# master_node_1284p.net
KiCad netlist of a schematic drawn in EAGLE
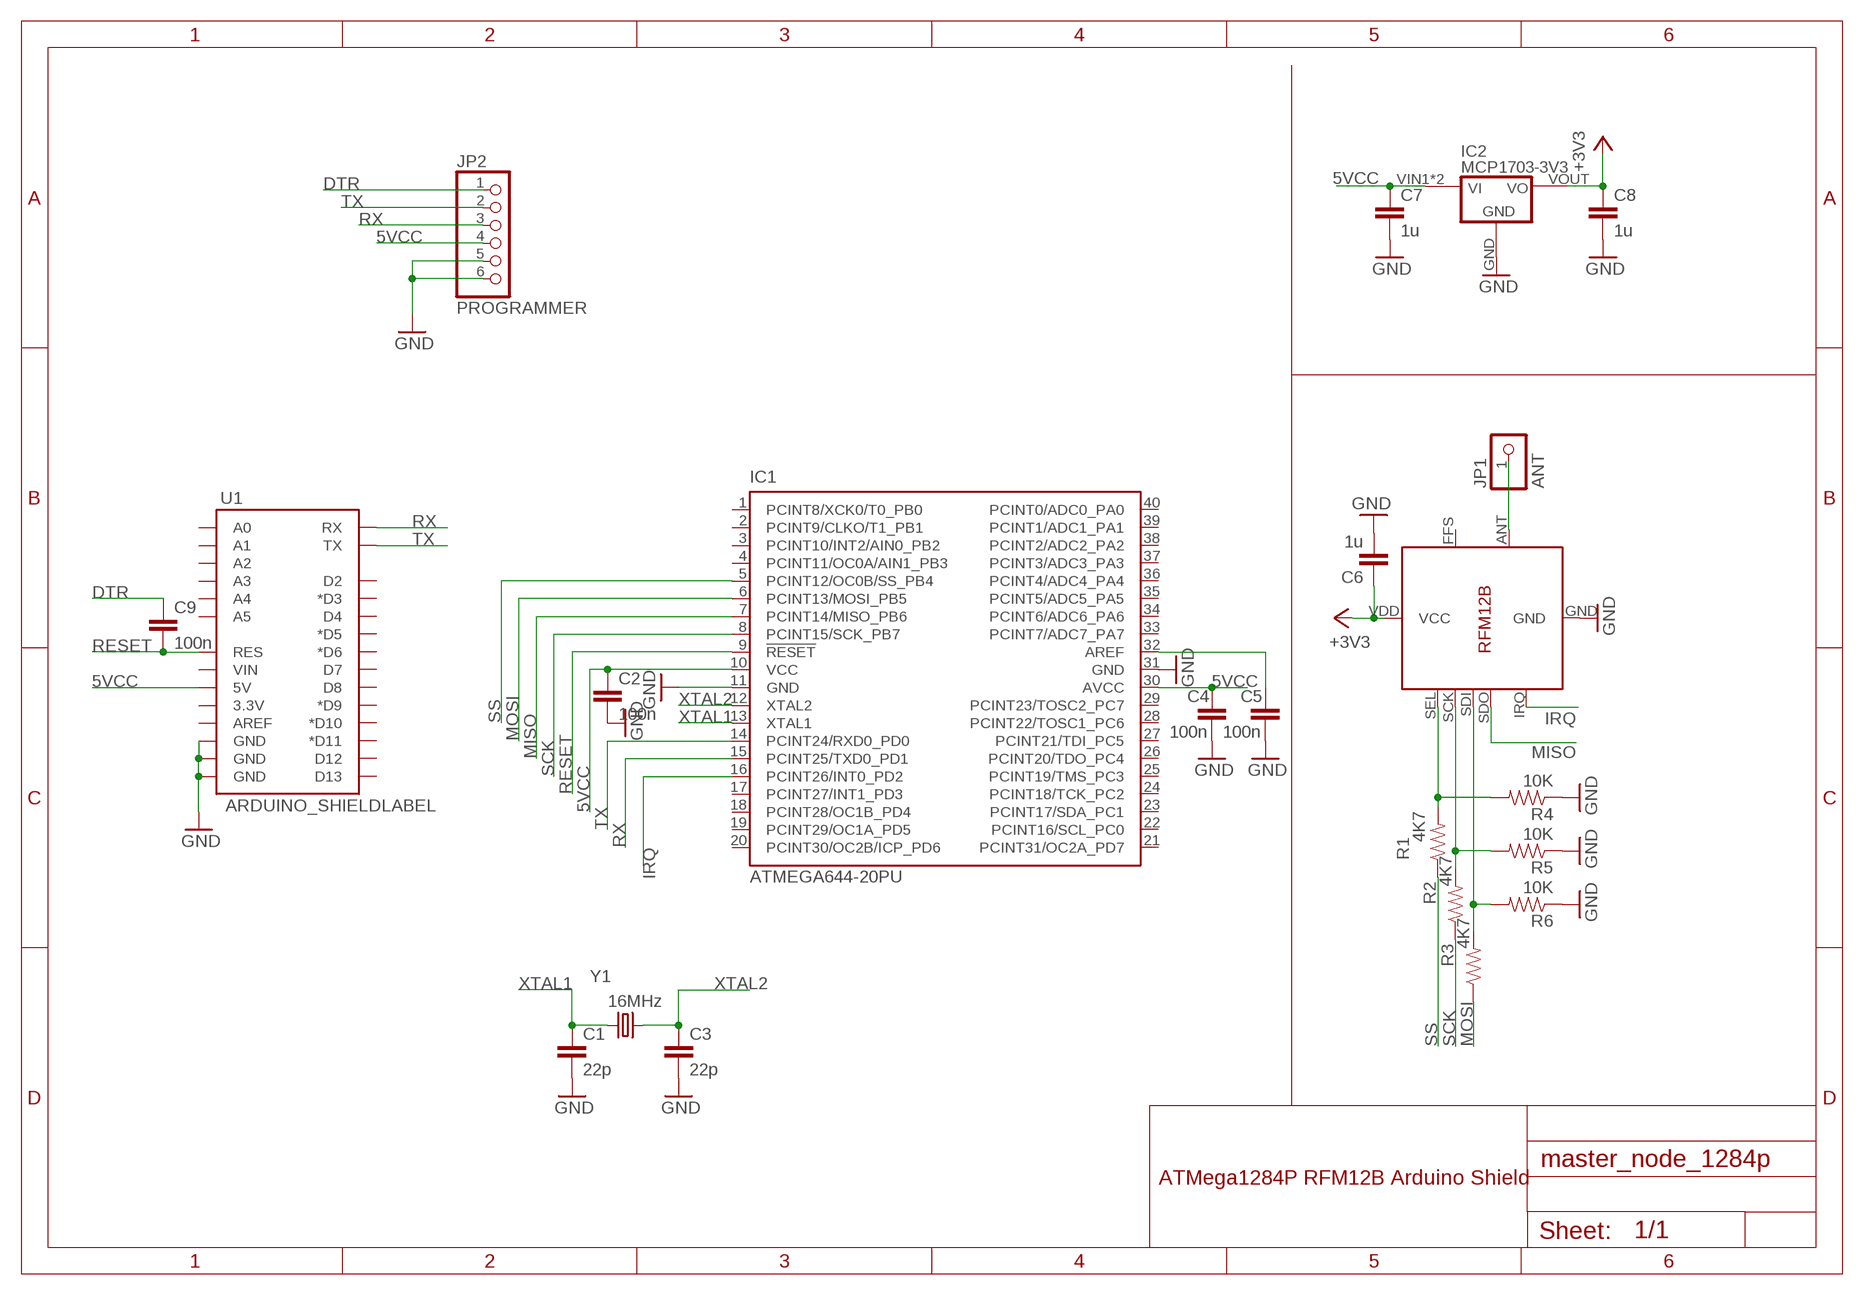
[diagram p0: schematic, sheet 1]

(export (version "E")
  (design (tool "Eeschema 10.0.6"))
  (components
    (comp (ref "C1")
      (value "22p")
      (footprint "eagle-import:C0805K")
      (libsource (lib "eagle-import") (part "C-EUC0805K"))
    )
    (comp (ref "C2")
      (value "100n")
      (footprint "eagle-import:C0805K")
      (libsource (lib "eagle-import") (part "C-EUC0805K"))
    )
    (comp (ref "C3")
      (value "22p")
      (footprint "eagle-import:C0805K")
      (libsource (lib "eagle-import") (part "C-EUC0805K"))
    )
    (comp (ref "C4")
      (value "100n")
      (footprint "eagle-import:C0805K")
      (libsource (lib "eagle-import") (part "C-EUC0805K"))
    )
    (comp (ref "C5")
      (value "100n")
      (footprint "eagle-import:C0805K")
      (libsource (lib "eagle-import") (part "C-EUC0805K"))
    )
    (comp (ref "C6")
      (value "1u")
      (footprint "eagle-import:0805")
      (libsource (lib "eagle-import") (part "CAP0805"))
    )
    (comp (ref "C7")
      (value "1u")
      (footprint "eagle-import:0805")
      (libsource (lib "eagle-import") (part "CAP0805"))
    )
    (comp (ref "C8")
      (value "1u")
      (footprint "eagle-import:0805")
      (libsource (lib "eagle-import") (part "CAP0805"))
    )
    (comp (ref "C9")
      (value "100n")
      (footprint "eagle-import:C0805K")
      (libsource (lib "eagle-import") (part "C-EUC0805K"))
    )
    (comp (ref "IC1")
      (value "ATMEGA644-20PU")
      (footprint "eagle-import:DIL40")
      (libsource (lib "eagle-import") (part "ATMEGA644-PU20"))
    )
    (comp (ref "IC2")
      (value "MCP1703-3V3")
      (footprint "eagle-import:MCP1703-SOT89")
      (libsource (lib "eagle-import") (part "MCP1703-SOT89"))
    )
    (comp (ref "JP1")
      (value "ANT")
      (footprint "eagle-import:1X01")
      (libsource (lib "eagle-import") (part "PINHD-1X1"))
    )
    (comp (ref "JP2")
      (value "PROGRAMMER")
      (footprint "eagle-import:1X06_90")
      (libsource (lib "eagle-import") (part "PINHD-1X6/90"))
    )
    (comp (ref "R1")
      (value "4K7")
      (footprint "eagle-import:0805")
      (libsource (lib "eagle-import") (part "RESISTOR0805-RES"))
    )
    (comp (ref "R2")
      (value "4K7")
      (footprint "eagle-import:0805")
      (libsource (lib "eagle-import") (part "RESISTOR0805-RES"))
    )
    (comp (ref "R3")
      (value "4K7")
      (footprint "eagle-import:0805")
      (libsource (lib "eagle-import") (part "RESISTOR0805-RES"))
    )
    (comp (ref "R4")
      (value "10K")
      (footprint "eagle-import:0805")
      (libsource (lib "eagle-import") (part "RESISTOR0805-RES"))
    )
    (comp (ref "R5")
      (value "10K")
      (footprint "eagle-import:0805")
      (libsource (lib "eagle-import") (part "RESISTOR0805-RES"))
    )
    (comp (ref "R6")
      (value "10K")
      (footprint "eagle-import:0805")
      (libsource (lib "eagle-import") (part "RESISTOR0805-RES"))
    )
    (comp (ref "U$1")
      (value "RFM12B")
      (footprint "eagle-import:RFM12B")
      (libsource (lib "eagle-import") (part "RFM12B"))
    )
    (comp (ref "U1")
      (value "ARDUINO_SHIELDLABEL")
      (footprint "eagle-import:DUEMILANOVE_SHIELD")
      (libsource (lib "eagle-import") (part "ARDUINO_SHIELDLABEL"))
    )
    (comp (ref "Y1")
      (value "16MHz")
      (footprint "eagle-import:HC49US")
      (libsource (lib "eagle-import") (part "CRYSTALHC49US"))
    )
  )
  (nets
    (net (code "1") (name "+3V3") (class "Default")
      (node (ref "C6") (pin "1") (pinfunction "1_1") (pintype "passive"))
      (node (ref "C8") (pin "1") (pinfunction "1_1") (pintype "passive"))
      (node (ref "IC2") (pin "VOUT") (pinfunction "VO_VOUT") (pintype "passive"))
      (node (ref "U$1") (pin "VDD") (pinfunction "VCC_VDD") (pintype "power_in"))
    )
    (net (code "2") (name "/5VCC") (class "Default")
      (node (ref "C2") (pin "1") (pinfunction "1_1") (pintype "passive"))
      (node (ref "C4") (pin "1") (pinfunction "1_1") (pintype "passive"))
      (node (ref "C7") (pin "1") (pinfunction "1_1") (pintype "passive"))
      (node (ref "IC1") (pin "10") (pinfunction "VCC_10") (pintype "power_in"))
      (node (ref "IC1") (pin "30") (pinfunction "AVCC_30") (pintype "power_in"))
      (node (ref "IC2") (pin "VIN1") (pinfunction "VI_VIN1") (pintype "power_in"))
      (node (ref "IC2") (pin "VIN2") (pinfunction "VI_VIN2") (pintype "power_in"))
      (node (ref "JP2") (pin "4") (pinfunction "4_4") (pintype "passive"))
      (node (ref "U1") (pin "5V") (pinfunction "5V_5V") (pintype "bidirectional"))
    )
    (net (code "3") (name "/DTR") (class "Default")
      (node (ref "C9") (pin "1") (pinfunction "1_1") (pintype "passive"))
      (node (ref "JP2") (pin "1") (pinfunction "1_1") (pintype "passive"))
    )
    (net (code "4") (name "/IRQ") (class "Default")
      (node (ref "IC1") (pin "16") (pinfunction "PCINT26/INT0_PD2_16") (pintype "bidirectional"))
      (node (ref "U$1") (pin "IRQ") (pinfunction "IRQ_IRQ") (pintype "open_collector"))
    )
    (net (code "5") (name "/MISO") (class "Default")
      (node (ref "IC1") (pin "7") (pinfunction "PCINT14/MISO_PB6_7") (pintype "bidirectional"))
      (node (ref "U$1") (pin "SDO") (pinfunction "SDO_SDO") (pintype "output"))
    )
    (net (code "6") (name "/MOSI") (class "Default")
      (node (ref "IC1") (pin "6") (pinfunction "PCINT13/MOSI_PB5_6") (pintype "bidirectional"))
      (node (ref "R3") (pin "1") (pinfunction "1_1") (pintype "passive"))
    )
    (net (code "7") (name "/RESET") (class "Default")
      (node (ref "C9") (pin "2") (pinfunction "2_2") (pintype "passive"))
      (node (ref "IC1") (pin "9") (pinfunction "~{RESET}_9") (pintype "input"))
      (node (ref "U1") (pin "RES") (pinfunction "RES_RES") (pintype "bidirectional"))
    )
    (net (code "8") (name "/RX") (class "Default")
      (node (ref "IC1") (pin "15") (pinfunction "PCINT25/TXD0_PD1_15") (pintype "bidirectional"))
      (node (ref "JP2") (pin "3") (pinfunction "3_3") (pintype "passive"))
      (node (ref "U1") (pin "RX") (pinfunction "RX_RX") (pintype "bidirectional"))
    )
    (net (code "9") (name "/SCK") (class "Default")
      (node (ref "IC1") (pin "8") (pinfunction "PCINT15/SCK_PB7_8") (pintype "bidirectional"))
      (node (ref "R2") (pin "1") (pinfunction "1_1") (pintype "passive"))
    )
    (net (code "10") (name "/SS") (class "Default")
      (node (ref "IC1") (pin "5") (pinfunction "PCINT12/OC0B/SS_PB4_5") (pintype "bidirectional"))
      (node (ref "R1") (pin "1") (pinfunction "1_1") (pintype "passive"))
    )
    (net (code "11") (name "/TX") (class "Default")
      (node (ref "IC1") (pin "14") (pinfunction "PCINT24/RXD0_PD0_14") (pintype "bidirectional"))
      (node (ref "JP2") (pin "2") (pinfunction "2_2") (pintype "passive"))
      (node (ref "U1") (pin "TX") (pinfunction "TX_TX") (pintype "bidirectional"))
    )
    (net (code "12") (name "/XTAL1") (class "Default")
      (node (ref "C1") (pin "1") (pinfunction "1_1") (pintype "passive"))
      (node (ref "IC1") (pin "13") (pinfunction "XTAL1_13") (pintype "input"))
      (node (ref "Y1") (pin "1") (pinfunction "1_1") (pintype "passive"))
    )
    (net (code "13") (name "/XTAL2") (class "Default")
      (node (ref "C3") (pin "1") (pinfunction "1_1") (pintype "passive"))
      (node (ref "IC1") (pin "12") (pinfunction "XTAL2_12") (pintype "output"))
      (node (ref "Y1") (pin "2") (pinfunction "2_2") (pintype "passive"))
    )
    (net (code "14") (name "GND") (class "Default")
      (node (ref "C1") (pin "2") (pinfunction "2_2") (pintype "passive"))
      (node (ref "C2") (pin "2") (pinfunction "2_2") (pintype "passive"))
      (node (ref "C3") (pin "2") (pinfunction "2_2") (pintype "passive"))
      (node (ref "C4") (pin "2") (pinfunction "2_2") (pintype "passive"))
      (node (ref "C5") (pin "2") (pinfunction "2_2") (pintype "passive"))
      (node (ref "C6") (pin "2") (pinfunction "2_2") (pintype "passive"))
      (node (ref "C7") (pin "2") (pinfunction "2_2") (pintype "passive"))
      (node (ref "C8") (pin "2") (pinfunction "2_2") (pintype "passive"))
      (node (ref "IC1") (pin "11") (pinfunction "GND_11") (pintype "power_in"))
      (node (ref "IC1") (pin "31") (pinfunction "GND_31") (pintype "power_in"))
      (node (ref "IC2") (pin "GND") (pinfunction "GND_GND") (pintype "power_in"))
      (node (ref "JP2") (pin "5") (pinfunction "5_5") (pintype "passive"))
      (node (ref "JP2") (pin "6") (pinfunction "6_6") (pintype "passive"))
      (node (ref "R4") (pin "1") (pinfunction "1_1") (pintype "passive"))
      (node (ref "R5") (pin "1") (pinfunction "1_1") (pintype "passive"))
      (node (ref "R6") (pin "1") (pinfunction "1_1") (pintype "passive"))
      (node (ref "U$1") (pin "GND") (pinfunction "GND_GND") (pintype "power_in"))
      (node (ref "U1") (pin "GND@0") (pinfunction "GND_GND@0") (pintype "bidirectional"))
      (node (ref "U1") (pin "GND@1") (pinfunction "GND_GND@1") (pintype "bidirectional"))
      (node (ref "U1") (pin "GND@2") (pinfunction "GND_GND@2") (pintype "bidirectional"))
    )
    (net (code "15") (name "Net-(IC1-AREF)") (class "Default")
      (node (ref "C5") (pin "1") (pinfunction "1_1") (pintype "passive"))
      (node (ref "IC1") (pin "32") (pinfunction "AREF_32") (pintype "passive"))
    )
    (net (code "16") (name "Net-(JP1-Pad1)") (class "Default")
      (node (ref "JP1") (pin "1") (pinfunction "1_1") (pintype "passive"))
      (node (ref "U$1") (pin "ANT") (pinfunction "ANT_ANT") (pintype "passive"))
    )
    (net (code "17") (name "Net-(R1-Pad2)") (class "Default")
      (node (ref "R1") (pin "2") (pinfunction "2_2") (pintype "passive"))
      (node (ref "R4") (pin "2") (pinfunction "2_2") (pintype "passive"))
      (node (ref "U$1") (pin "SEL") (pinfunction "SEL_SEL") (pintype "input"))
    )
    (net (code "18") (name "Net-(R2-Pad2)") (class "Default")
      (node (ref "R2") (pin "2") (pinfunction "2_2") (pintype "passive"))
      (node (ref "R5") (pin "2") (pinfunction "2_2") (pintype "passive"))
      (node (ref "U$1") (pin "SCK") (pinfunction "SCK_SCK") (pintype "input"))
    )
    (net (code "19") (name "Net-(R3-Pad2)") (class "Default")
      (node (ref "R3") (pin "2") (pinfunction "2_2") (pintype "passive"))
      (node (ref "R6") (pin "2") (pinfunction "2_2") (pintype "passive"))
      (node (ref "U$1") (pin "SDI") (pinfunction "SDI_SDI") (pintype "input"))
    )
    (net (code "20") (name "unconnected-(IC1-PCINT0{slash}ADC0_PA0-Pad40)") (class "Default")
      (node (ref "IC1") (pin "40") (pinfunction "PCINT0/ADC0_PA0_40") (pintype "bidirectional"))
    )
    (net (code "21") (name "unconnected-(IC1-PCINT1{slash}ADC1_PA1-Pad39)") (class "Default")
      (node (ref "IC1") (pin "39") (pinfunction "PCINT1/ADC1_PA1_39") (pintype "bidirectional"))
    )
    (net (code "22") (name "unconnected-(IC1-PCINT2{slash}ADC2_PA2-Pad38)") (class "Default")
      (node (ref "IC1") (pin "38") (pinfunction "PCINT2/ADC2_PA2_38") (pintype "bidirectional"))
    )
    (net (code "23") (name "unconnected-(IC1-PCINT3{slash}ADC3_PA3-Pad37)") (class "Default")
      (node (ref "IC1") (pin "37") (pinfunction "PCINT3/ADC3_PA3_37") (pintype "bidirectional"))
    )
    (net (code "24") (name "unconnected-(IC1-PCINT4{slash}ADC4_PA4-Pad36)") (class "Default")
      (node (ref "IC1") (pin "36") (pinfunction "PCINT4/ADC4_PA4_36") (pintype "bidirectional"))
    )
    (net (code "25") (name "unconnected-(IC1-PCINT5{slash}ADC5_PA5-Pad35)") (class "Default")
      (node (ref "IC1") (pin "35") (pinfunction "PCINT5/ADC5_PA5_35") (pintype "bidirectional"))
    )
    (net (code "26") (name "unconnected-(IC1-PCINT6{slash}ADC6_PA6-Pad34)") (class "Default")
      (node (ref "IC1") (pin "34") (pinfunction "PCINT6/ADC6_PA6_34") (pintype "bidirectional"))
    )
    (net (code "27") (name "unconnected-(IC1-PCINT7{slash}ADC7_PA7-Pad33)") (class "Default")
      (node (ref "IC1") (pin "33") (pinfunction "PCINT7/ADC7_PA7_33") (pintype "bidirectional"))
    )
    (net (code "28") (name "unconnected-(IC1-PCINT8{slash}XCK0{slash}T0_PB0-Pad1)") (class "Default")
      (node (ref "IC1") (pin "1") (pinfunction "PCINT8/XCK0/T0_PB0_1") (pintype "bidirectional"))
    )
    (net (code "29") (name "unconnected-(IC1-PCINT9{slash}CLKO{slash}T1_PB1-Pad2)") (class "Default")
      (node (ref "IC1") (pin "2") (pinfunction "PCINT9/CLKO/T1_PB1_2") (pintype "bidirectional"))
    )
    (net (code "30") (name "unconnected-(IC1-PCINT10{slash}INT2{slash}AIN0_PB2-Pad3)") (class "Default")
      (node (ref "IC1") (pin "3") (pinfunction "PCINT10/INT2/AIN0_PB2_3") (pintype "bidirectional"))
    )
    (net (code "31") (name "unconnected-(IC1-PCINT11{slash}OC0A{slash}AIN1_PB3-Pad4)") (class "Default")
      (node (ref "IC1") (pin "4") (pinfunction "PCINT11/OC0A/AIN1_PB3_4") (pintype "bidirectional"))
    )
    (net (code "32") (name "unconnected-(IC1-PCINT16{slash}SCL_PC0-Pad22)") (class "Default")
      (node (ref "IC1") (pin "22") (pinfunction "PCINT16/SCL_PC0_22") (pintype "bidirectional"))
    )
    (net (code "33") (name "unconnected-(IC1-PCINT17{slash}SDA_PC1-Pad23)") (class "Default")
      (node (ref "IC1") (pin "23") (pinfunction "PCINT17/SDA_PC1_23") (pintype "bidirectional"))
    )
    (net (code "34") (name "unconnected-(IC1-PCINT18{slash}TCK_PC2-Pad24)") (class "Default")
      (node (ref "IC1") (pin "24") (pinfunction "PCINT18/TCK_PC2_24") (pintype "bidirectional"))
    )
    (net (code "35") (name "unconnected-(IC1-PCINT19{slash}TMS_PC3-Pad25)") (class "Default")
      (node (ref "IC1") (pin "25") (pinfunction "PCINT19/TMS_PC3_25") (pintype "bidirectional"))
    )
    (net (code "36") (name "unconnected-(IC1-PCINT20{slash}TDO_PC4-Pad26)") (class "Default")
      (node (ref "IC1") (pin "26") (pinfunction "PCINT20/TDO_PC4_26") (pintype "bidirectional"))
    )
    (net (code "37") (name "unconnected-(IC1-PCINT21{slash}TDI_PC5-Pad27)") (class "Default")
      (node (ref "IC1") (pin "27") (pinfunction "PCINT21/TDI_PC5_27") (pintype "bidirectional"))
    )
    (net (code "38") (name "unconnected-(IC1-PCINT22{slash}TOSC1_PC6-Pad28)") (class "Default")
      (node (ref "IC1") (pin "28") (pinfunction "PCINT22/TOSC1_PC6_28") (pintype "bidirectional"))
    )
    (net (code "39") (name "unconnected-(IC1-PCINT23{slash}TOSC2_PC7-Pad29)") (class "Default")
      (node (ref "IC1") (pin "29") (pinfunction "PCINT23/TOSC2_PC7_29") (pintype "bidirectional"))
    )
    (net (code "40") (name "unconnected-(IC1-PCINT27{slash}INT1_PD3-Pad17)") (class "Default")
      (node (ref "IC1") (pin "17") (pinfunction "PCINT27/INT1_PD3_17") (pintype "bidirectional"))
    )
    (net (code "41") (name "unconnected-(IC1-PCINT28{slash}OC1B_PD4-Pad18)") (class "Default")
      (node (ref "IC1") (pin "18") (pinfunction "PCINT28/OC1B_PD4_18") (pintype "bidirectional"))
    )
    (net (code "42") (name "unconnected-(IC1-PCINT29{slash}OC1A_PD5-Pad19)") (class "Default")
      (node (ref "IC1") (pin "19") (pinfunction "PCINT29/OC1A_PD5_19") (pintype "bidirectional"))
    )
    (net (code "43") (name "unconnected-(IC1-PCINT30{slash}OC2B{slash}ICP_PD6-Pad20)") (class "Default")
      (node (ref "IC1") (pin "20") (pinfunction "PCINT30/OC2B/ICP_PD6_20") (pintype "bidirectional"))
    )
    (net (code "44") (name "unconnected-(IC1-PCINT31{slash}OC2A_PD7-Pad21)") (class "Default")
      (node (ref "IC1") (pin "21") (pinfunction "PCINT31/OC2A_PD7_21") (pintype "bidirectional"))
    )
    (net (code "45") (name "unconnected-(U$1-PadFFS)") (class "Default")
      (node (ref "U$1") (pin "FFS") (pinfunction "FFS_FFS") (pintype "bidirectional"))
    )
    (net (code "46") (name "unconnected-(U1-*D3-PadD3)") (class "Default")
      (node (ref "U1") (pin "D3") (pinfunction "*D3_D3") (pintype "bidirectional"))
    )
    (net (code "47") (name "unconnected-(U1-*D5-PadD5)") (class "Default")
      (node (ref "U1") (pin "D5") (pinfunction "*D5_D5") (pintype "bidirectional"))
    )
    (net (code "48") (name "unconnected-(U1-*D6-PadD6)") (class "Default")
      (node (ref "U1") (pin "D6") (pinfunction "*D6_D6") (pintype "bidirectional"))
    )
    (net (code "49") (name "unconnected-(U1-*D9-PadD9)") (class "Default")
      (node (ref "U1") (pin "D9") (pinfunction "*D9_D9") (pintype "bidirectional"))
    )
    (net (code "50") (name "unconnected-(U1-*D10-PadD10)") (class "Default")
      (node (ref "U1") (pin "D10") (pinfunction "*D10_D10") (pintype "bidirectional"))
    )
    (net (code "51") (name "unconnected-(U1-*D11-PadD11)") (class "Default")
      (node (ref "U1") (pin "D11") (pinfunction "*D11_D11") (pintype "bidirectional"))
    )
    (net (code "52") (name "unconnected-(U1-Pad3.3V)") (class "Default")
      (node (ref "U1") (pin "3.3V") (pinfunction "3.3V_3.3V") (pintype "bidirectional"))
    )
    (net (code "53") (name "unconnected-(U1-PadA0)") (class "Default")
      (node (ref "U1") (pin "A0") (pinfunction "A0_A0") (pintype "bidirectional"))
    )
    (net (code "54") (name "unconnected-(U1-PadA1)") (class "Default")
      (node (ref "U1") (pin "A1") (pinfunction "A1_A1") (pintype "bidirectional"))
    )
    (net (code "55") (name "unconnected-(U1-PadA2)") (class "Default")
      (node (ref "U1") (pin "A2") (pinfunction "A2_A2") (pintype "bidirectional"))
    )
    (net (code "56") (name "unconnected-(U1-PadA3)") (class "Default")
      (node (ref "U1") (pin "A3") (pinfunction "A3_A3") (pintype "bidirectional"))
    )
    (net (code "57") (name "unconnected-(U1-PadA4)") (class "Default")
      (node (ref "U1") (pin "A4") (pinfunction "A4_A4") (pintype "bidirectional"))
    )
    (net (code "58") (name "unconnected-(U1-PadA5)") (class "Default")
      (node (ref "U1") (pin "A5") (pinfunction "A5_A5") (pintype "bidirectional"))
    )
    (net (code "59") (name "unconnected-(U1-PadAREF)") (class "Default")
      (node (ref "U1") (pin "AREF") (pinfunction "AREF_AREF") (pintype "bidirectional"))
    )
    (net (code "60") (name "unconnected-(U1-PadD2)") (class "Default")
      (node (ref "U1") (pin "D2") (pinfunction "D2_D2") (pintype "bidirectional"))
    )
    (net (code "61") (name "unconnected-(U1-PadD4)") (class "Default")
      (node (ref "U1") (pin "D4") (pinfunction "D4_D4") (pintype "bidirectional"))
    )
    (net (code "62") (name "unconnected-(U1-PadD7)") (class "Default")
      (node (ref "U1") (pin "D7") (pinfunction "D7_D7") (pintype "bidirectional"))
    )
    (net (code "63") (name "unconnected-(U1-PadD8)") (class "Default")
      (node (ref "U1") (pin "D8") (pinfunction "D8_D8") (pintype "bidirectional"))
    )
    (net (code "64") (name "unconnected-(U1-PadD12)") (class "Default")
      (node (ref "U1") (pin "D12") (pinfunction "D12_D12") (pintype "bidirectional"))
    )
    (net (code "65") (name "unconnected-(U1-PadD13)") (class "Default")
      (node (ref "U1") (pin "D13") (pinfunction "D13_D13") (pintype "bidirectional"))
    )
    (net (code "66") (name "unconnected-(U1-PadVIN)") (class "Default")
      (node (ref "U1") (pin "VIN") (pinfunction "VIN_VIN") (pintype "bidirectional"))
    )
  )
)
